# Solenoid_drivers.net
KiCad netlist of a schematic drawn in Altium Designer
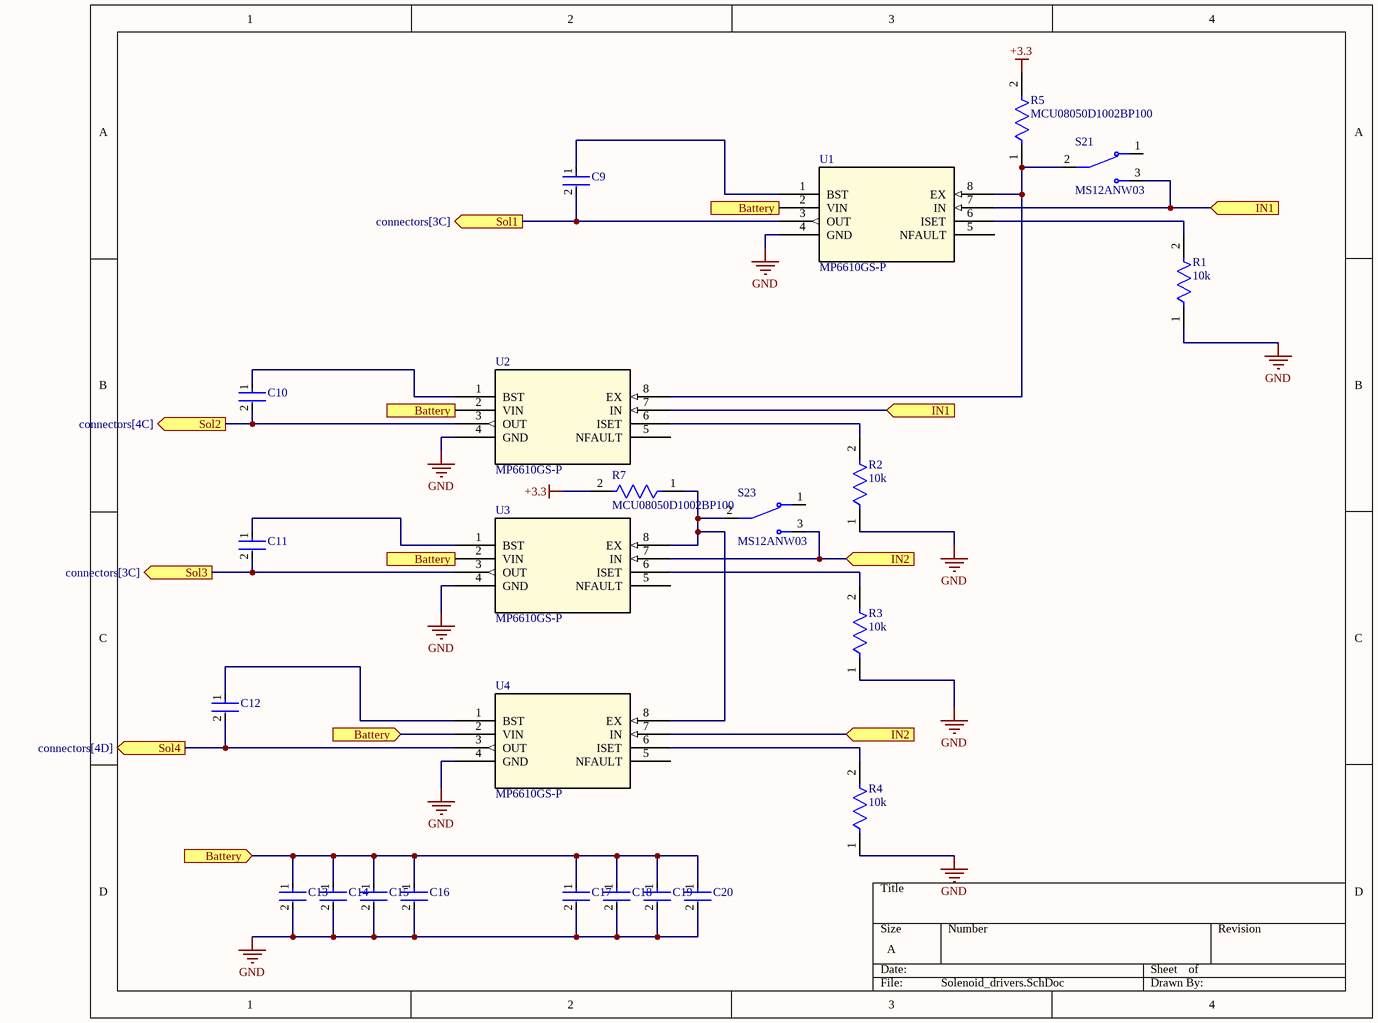
[diagram p0: Solenoid_drivers.SchDoc]

(export (version "E")
  (design (tool "Eeschema 10.0.6"))
  (components
    (comp (ref "C9")
      (value "C0805C104K5RACTU")
      (footprint "FP-C0805C-DN-MFG")
      (description "CAP CER 0.1UF 50V X7R 0805")
      (fields
        (field (name "MANUFACTURER") "KEMET")
        (field (name "OCTOPART") "https://octopart.com/c0805c104k5ractu-kemet-143926")
      )
      (libsource (lib "Altium Content Vault") (part "b4654b650e69147ec39a6b967a45e02"))
    )
    (comp (ref "C10")
      (value "C0805C104K5RACTU")
      (footprint "FP-C0805C-DN-MFG")
      (description "CAP CER 0.1UF 50V X7R 0805")
      (fields
        (field (name "MANUFACTURER") "KEMET")
        (field (name "OCTOPART") "https://octopart.com/c0805c104k5ractu-kemet-143926")
      )
      (libsource (lib "Altium Content Vault") (part "b4654b650e69147ec39a6b967a45e02"))
    )
    (comp (ref "C11")
      (value "C0805C104K5RACTU")
      (footprint "FP-C0805C-DN-MFG")
      (description "CAP CER 0.1UF 50V X7R 0805")
      (fields
        (field (name "MANUFACTURER") "KEMET")
        (field (name "OCTOPART") "https://octopart.com/c0805c104k5ractu-kemet-143926")
      )
      (libsource (lib "Altium Content Vault") (part "b4654b650e69147ec39a6b967a45e02"))
    )
    (comp (ref "C12")
      (value "C0805C104K5RACTU")
      (footprint "FP-C0805C-DN-MFG")
      (description "CAP CER 0.1UF 50V X7R 0805 C0805C104K5RACTU")
      (fields
        (field (name "MANUFACTURER") "KEMET")
        (field (name "OCTOPART") "https://octopart.com/c0805c104k5ractu-kemet-143926")
      )
      (libsource (lib "Altium Content Vault") (part "b4654b650e69147ec39a6b967a45e02"))
    )
    (comp (ref "C13")
      (value "C0805C104K5RACTU")
      (footprint "FP-C0805C-DN-MFG")
      (description "CAP CER 0.1UF 50V X7R 0805")
      (fields
        (field (name "MANUFACTURER") "KEMET")
        (field (name "OCTOPART") "https://octopart.com/c0805c104k5ractu-kemet-143926")
      )
      (libsource (lib "Altium Content Vault") (part "b4654b650e69147ec39a6b967a45e02"))
    )
    (comp (ref "C14")
      (value "C0805C104K5RACTU")
      (footprint "FP-C0805C-DN-MFG")
      (description "CAP CER 0.1UF 50V X7R 0805")
      (fields
        (field (name "MANUFACTURER") "KEMET")
        (field (name "OCTOPART") "https://octopart.com/c0805c104k5ractu-kemet-143926")
      )
      (libsource (lib "Altium Content Vault") (part "b4654b650e69147ec39a6b967a45e02"))
    )
    (comp (ref "C15")
      (value "C0805C104K5RACTU")
      (footprint "FP-C0805C-DN-MFG")
      (description "CAP CER 0.1UF 50V X7R 0805")
      (fields
        (field (name "MANUFACTURER") "KEMET")
        (field (name "OCTOPART") "https://octopart.com/c0805c104k5ractu-kemet-143926")
      )
      (libsource (lib "Altium Content Vault") (part "b4654b650e69147ec39a6b967a45e02"))
    )
    (comp (ref "C16")
      (value "C0805C104K5RACTU")
      (footprint "FP-C0805C-DN-MFG")
      (description "CAP CER 0.1UF 50V X7R 0805")
      (fields
        (field (name "MANUFACTURER") "KEMET")
        (field (name "OCTOPART") "https://octopart.com/c0805c104k5ractu-kemet-143926")
      )
      (libsource (lib "Altium Content Vault") (part "b4654b650e69147ec39a6b967a45e02"))
    )
    (comp (ref "C17")
      (value "GRM21BR6YA106ME43L")
      (footprint "FP-GRM21B-0_2-e0_2_0_7-IPC_B")
      (description "Chip Multilayer Ceramic Capacitors for General Purpose, 0805, 10uF, X5R, 15%, 20%, 35V")
      (fields (field (name "TOLERANCE") "20%"))
      (libsource (lib "Altium Content Vault") (part "b4654b650e69147ec39a6b967a45e02"))
    )
    (comp (ref "C18")
      (value "GRM21BR6YA106ME43L")
      (footprint "FP-GRM21B-0_2-e0_2_0_7-IPC_B")
      (description "Chip Multilayer Ceramic Capacitors for General Purpose, 0805, 10uF, X5R, 15%, 20%, 35V")
      (fields (field (name "TOLERANCE") "20%"))
      (libsource (lib "Altium Content Vault") (part "b4654b650e69147ec39a6b967a45e02"))
    )
    (comp (ref "C19")
      (value "GRM21BR6YA106ME43L")
      (footprint "FP-GRM21B-0_2-e0_2_0_7-IPC_B")
      (description "Chip Multilayer Ceramic Capacitors for General Purpose, 0805, 10uF, X5R, 15%, 20%, 35V")
      (fields (field (name "TOLERANCE") "20%"))
      (libsource (lib "Altium Content Vault") (part "b4654b650e69147ec39a6b967a45e02"))
    )
    (comp (ref "C20")
      (value "GRM21BR6YA106ME43L")
      (footprint "FP-GRM21B-0_2-e0_2_0_7-IPC_B")
      (description "Chip Multilayer Ceramic Capacitors for General Purpose, 0805, 10uF, X5R, 15%, 20%, 35V")
      (fields (field (name "TOLERANCE") "20%"))
      (libsource (lib "Altium Content Vault") (part "b4654b650e69147ec39a6b967a45e02"))
    )
    (comp (ref "R1")
      (value "10k")
      (footprint "FP-MCU0805-IPC_C")
      (description "RES 1.05K OHM 0.5% 1/5W 0805   MCU08050D1002BP100")
      (fields (field (name "TOLERANCE") "0.1%"))
      (libsource (lib "Altium Content Vault") (part "1029c3af85768c4190bb7ad29bc67b5"))
    )
    (comp (ref "R2")
      (value "10k")
      (footprint "FP-MCU0805-IPC_C")
      (description "RES 1.05K OHM 0.5% 1/5W 0805   MCU08050D1002BP100")
      (fields (field (name "TOLERANCE") "0.1%"))
      (libsource (lib "Altium Content Vault") (part "1029c3af85768c4190bb7ad29bc67b5"))
    )
    (comp (ref "R3")
      (value "10k")
      (footprint "FP-MCU0805-IPC_C")
      (description "RES 1.05K OHM 0.5% 1/5W 0805   MCU08050D1002BP100")
      (fields (field (name "TOLERANCE") "0.1%"))
      (libsource (lib "Altium Content Vault") (part "1029c3af85768c4190bb7ad29bc67b5"))
    )
    (comp (ref "R4")
      (value "10k")
      (footprint "FP-MCU0805-IPC_C")
      (description "RES 1.05K OHM 0.5% 1/5W 0805   MCU08050D1002BP100")
      (fields (field (name "TOLERANCE") "0.1%"))
      (libsource (lib "Altium Content Vault") (part "1029c3af85768c4190bb7ad29bc67b5"))
    )
    (comp (ref "R5")
      (value "MCU08050D1002BP100")
      (footprint "FP-MCU0805-IPC_C")
      (description "RES 1.05K OHM 0.5% 1/5W 0805")
      (fields (field (name "TOLERANCE") "0.1%"))
      (libsource (lib "Altium Content Vault") (part "1029c3af85768c4190bb7ad29bc67b5"))
    )
    (comp (ref "R7")
      (value "MCU08050D1002BP100")
      (footprint "FP-MCU0805-IPC_C")
      (description "RES 1.05K OHM 0.5% 1/5W 0805")
      (fields (field (name "TOLERANCE") "0.1%"))
      (libsource (lib "Altium Content Vault") (part "1029c3af85768c4190bb7ad29bc67b5"))
    )
    (comp (ref "S21")
      (value "MS12ANW03")
      (footprint "SW_MS12ANW03")
      (description "Slide Switch SPDT Through Hole")
      (fields (field (name "MF") "NKK Switches"))
      (libsource (lib "SnapEDAsch") (part "MS12ANW03"))
    )
    (comp (ref "S23")
      (value "MS12ANW03")
      (footprint "SW_MS12ANW03")
      (description "Slide Switch SPDT Through Hole")
      (fields (field (name "MF") "NKK Switches"))
      (libsource (lib "SnapEDAsch") (part "MS12ANW03"))
    )
    (comp (ref "U1")
      (value "MP6610GS-P")
      (footprint "SOIC-8_MP6610_MNP")
      (description "No Description Available")
      (libsource (lib "MP6610GS-P") (part "MP6610GS-P"))
    )
    (comp (ref "U2")
      (value "MP6610GS-P")
      (footprint "SOIC-8_MP6610_MNP")
      (description "No Description Available")
      (libsource (lib "MP6610GS-P") (part "MP6610GS-P"))
    )
    (comp (ref "U3")
      (value "MP6610GS-P")
      (footprint "SOIC-8_MP6610_MNP")
      (description "No Description Available")
      (libsource (lib "MP6610GS-P") (part "MP6610GS-P"))
    )
    (comp (ref "U4")
      (value "MP6610GS-P")
      (footprint "SOIC-8_MP6610_MNP")
      (description "No Description Available")
      (libsource (lib "MP6610GS-P") (part "MP6610GS-P"))
    )
  )
  (nets
    (net (code "1") (name "+3.3") (class "Default")
      (node (ref "R5") (pin "2") (pinfunction "2_2") (pintype "passive"))
      (node (ref "R7") (pin "2") (pinfunction "2_2") (pintype "passive"))
    )
    (net (code "2") (name "/Battery") (class "Default")
      (node (ref "C13") (pin "1") (pinfunction "1_1") (pintype "passive"))
      (node (ref "C14") (pin "1") (pinfunction "1_1") (pintype "passive"))
      (node (ref "C15") (pin "1") (pinfunction "1_1") (pintype "passive"))
      (node (ref "C16") (pin "1") (pinfunction "1_1") (pintype "passive"))
      (node (ref "C17") (pin "1") (pinfunction "1_1") (pintype "passive"))
      (node (ref "C18") (pin "1") (pinfunction "1_1") (pintype "passive"))
      (node (ref "C19") (pin "1") (pinfunction "1_1") (pintype "passive"))
      (node (ref "C20") (pin "1") (pinfunction "1_1") (pintype "passive"))
      (node (ref "U1") (pin "2") (pinfunction "VIN_2") (pintype "power_in"))
      (node (ref "U2") (pin "2") (pinfunction "VIN_2") (pintype "power_in"))
      (node (ref "U3") (pin "2") (pinfunction "VIN_2") (pintype "power_in"))
      (node (ref "U4") (pin "2") (pinfunction "VIN_2") (pintype "power_in"))
    )
    (net (code "3") (name "/IN1") (class "Default")
      (node (ref "S21") (pin "3") (pinfunction "3_3") (pintype "passive"))
      (node (ref "U1") (pin "7") (pinfunction "IN_7") (pintype "input"))
      (node (ref "U2") (pin "7") (pinfunction "IN_7") (pintype "input"))
    )
    (net (code "4") (name "/IN2") (class "Default")
      (node (ref "S23") (pin "3") (pinfunction "3_3") (pintype "passive"))
      (node (ref "U3") (pin "7") (pinfunction "IN_7") (pintype "input"))
      (node (ref "U4") (pin "7") (pinfunction "IN_7") (pintype "input"))
    )
    (net (code "5") (name "/Sol1") (class "Default")
      (node (ref "C9") (pin "2") (pinfunction "2_2") (pintype "passive"))
      (node (ref "U1") (pin "3") (pinfunction "OUT_3") (pintype "output"))
    )
    (net (code "6") (name "/Sol2") (class "Default")
      (node (ref "C10") (pin "2") (pinfunction "2_2") (pintype "passive"))
      (node (ref "U2") (pin "3") (pinfunction "OUT_3") (pintype "output"))
    )
    (net (code "7") (name "/Sol3") (class "Default")
      (node (ref "C11") (pin "2") (pinfunction "2_2") (pintype "passive"))
      (node (ref "U3") (pin "3") (pinfunction "OUT_3") (pintype "output"))
    )
    (net (code "8") (name "/Sol4") (class "Default")
      (node (ref "C12") (pin "2") (pinfunction "2_2") (pintype "passive"))
      (node (ref "U4") (pin "3") (pinfunction "OUT_3") (pintype "output"))
    )
    (net (code "9") (name "GND") (class "Default")
      (node (ref "C13") (pin "2") (pinfunction "2_2") (pintype "passive"))
      (node (ref "C14") (pin "2") (pinfunction "2_2") (pintype "passive"))
      (node (ref "C15") (pin "2") (pinfunction "2_2") (pintype "passive"))
      (node (ref "C16") (pin "2") (pinfunction "2_2") (pintype "passive"))
      (node (ref "C17") (pin "2") (pinfunction "2_2") (pintype "passive"))
      (node (ref "C18") (pin "2") (pinfunction "2_2") (pintype "passive"))
      (node (ref "C19") (pin "2") (pinfunction "2_2") (pintype "passive"))
      (node (ref "C20") (pin "2") (pinfunction "2_2") (pintype "passive"))
      (node (ref "R1") (pin "1") (pinfunction "1_1") (pintype "passive"))
      (node (ref "R2") (pin "1") (pinfunction "1_1") (pintype "passive"))
      (node (ref "R3") (pin "1") (pinfunction "1_1") (pintype "passive"))
      (node (ref "R4") (pin "1") (pinfunction "1_1") (pintype "passive"))
      (node (ref "U1") (pin "4") (pinfunction "GND_4") (pintype "power_in"))
      (node (ref "U2") (pin "4") (pinfunction "GND_4") (pintype "power_in"))
      (node (ref "U3") (pin "4") (pinfunction "GND_4") (pintype "power_in"))
      (node (ref "U4") (pin "4") (pinfunction "GND_4") (pintype "power_in"))
    )
    (net (code "10") (name "Net-(U1-BST)") (class "Default")
      (node (ref "C9") (pin "1") (pinfunction "1_1") (pintype "passive"))
      (node (ref "U1") (pin "1") (pinfunction "BST_1") (pintype "passive"))
    )
    (net (code "11") (name "Net-(U1-EX)") (class "Default")
      (node (ref "R5") (pin "1") (pinfunction "1_1") (pintype "passive"))
      (node (ref "S21") (pin "2") (pinfunction "2_2") (pintype "passive"))
      (node (ref "U1") (pin "8") (pinfunction "EX_8") (pintype "input"))
      (node (ref "U2") (pin "8") (pinfunction "EX_8") (pintype "input"))
    )
    (net (code "12") (name "Net-(U1-ISET)") (class "Default")
      (node (ref "R1") (pin "2") (pinfunction "2_2") (pintype "passive"))
      (node (ref "U1") (pin "6") (pinfunction "ISET_6") (pintype "passive"))
    )
    (net (code "13") (name "Net-(U2-BST)") (class "Default")
      (node (ref "C10") (pin "1") (pinfunction "1_1") (pintype "passive"))
      (node (ref "U2") (pin "1") (pinfunction "BST_1") (pintype "passive"))
    )
    (net (code "14") (name "Net-(U2-ISET)") (class "Default")
      (node (ref "R2") (pin "2") (pinfunction "2_2") (pintype "passive"))
      (node (ref "U2") (pin "6") (pinfunction "ISET_6") (pintype "passive"))
    )
    (net (code "15") (name "Net-(U3-BST)") (class "Default")
      (node (ref "C11") (pin "1") (pinfunction "1_1") (pintype "passive"))
      (node (ref "U3") (pin "1") (pinfunction "BST_1") (pintype "passive"))
    )
    (net (code "16") (name "Net-(U3-EX)") (class "Default")
      (node (ref "R7") (pin "1") (pinfunction "1_1") (pintype "passive"))
      (node (ref "S23") (pin "2") (pinfunction "2_2") (pintype "passive"))
      (node (ref "U3") (pin "8") (pinfunction "EX_8") (pintype "input"))
      (node (ref "U4") (pin "8") (pinfunction "EX_8") (pintype "input"))
    )
    (net (code "17") (name "Net-(U3-ISET)") (class "Default")
      (node (ref "R3") (pin "2") (pinfunction "2_2") (pintype "passive"))
      (node (ref "U3") (pin "6") (pinfunction "ISET_6") (pintype "passive"))
    )
    (net (code "18") (name "Net-(U4-BST)") (class "Default")
      (node (ref "C12") (pin "1") (pinfunction "1_1") (pintype "passive"))
      (node (ref "U4") (pin "1") (pinfunction "BST_1") (pintype "passive"))
    )
    (net (code "19") (name "Net-(U4-ISET)") (class "Default")
      (node (ref "R4") (pin "2") (pinfunction "2_2") (pintype "passive"))
      (node (ref "U4") (pin "6") (pinfunction "ISET_6") (pintype "passive"))
    )
    (net (code "20") (name "unconnected-(S21-Pad1)") (class "Default")
      (node (ref "S21") (pin "1") (pinfunction "1_1") (pintype "passive"))
    )
    (net (code "21") (name "unconnected-(S23-Pad1)") (class "Default")
      (node (ref "S23") (pin "1") (pinfunction "1_1") (pintype "passive"))
    )
    (net (code "22") (name "unconnected-(U1-NFAULT-Pad5)") (class "Default")
      (node (ref "U1") (pin "5") (pinfunction "NFAULT_5") (pintype "passive"))
    )
    (net (code "23") (name "unconnected-(U2-NFAULT-Pad5)") (class "Default")
      (node (ref "U2") (pin "5") (pinfunction "NFAULT_5") (pintype "passive"))
    )
    (net (code "24") (name "unconnected-(U3-NFAULT-Pad5)") (class "Default")
      (node (ref "U3") (pin "5") (pinfunction "NFAULT_5") (pintype "passive"))
    )
    (net (code "25") (name "unconnected-(U4-NFAULT-Pad5)") (class "Default")
      (node (ref "U4") (pin "5") (pinfunction "NFAULT_5") (pintype "passive"))
    )
  )
)
